# main.net
KiCad netlist of a schematic drawn in EAGLE
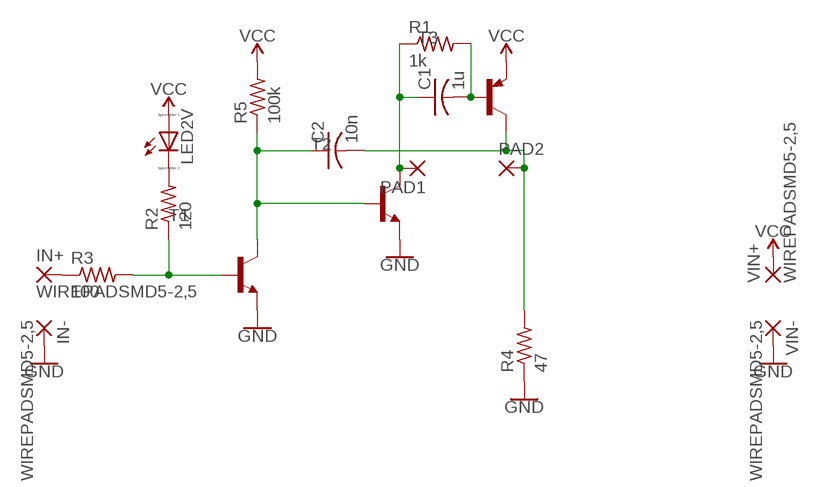
[diagram p0: schematic, sheet 1]

(export (version "E")
  (design (tool "Eeschema 10.0.6"))
  (components
    (comp (ref "C1")
      (value "1u")
      (footprint "eagle-import:C0603")
      (libsource (lib "eagle-import") (part "C-USC0603"))
    )
    (comp (ref "C2")
      (value "10n")
      (footprint "eagle-import:C0603")
      (libsource (lib "eagle-import") (part "C-USC0603"))
    )
    (comp (ref "IN+")
      (value "WIREPADSMD5-2,5")
      (footprint "eagle-import:5-2,5")
      (libsource (lib "eagle-import") (part "WIREPADSMD5-2,5"))
    )
    (comp (ref "IN-")
      (value "WIREPADSMD5-2,5")
      (footprint "eagle-import:5-2,5")
      (libsource (lib "eagle-import") (part "WIREPADSMD5-2,5"))
    )
    (comp (ref "LED2V")
      (value "LED_ESML0603")
      (footprint "eagle-import:LED_SML0603")
      (libsource (lib "eagle-import") (part "LED_ESML0603"))
    )
    (comp (ref "PAD1")
      (value "2,54/1,0")
      (footprint "eagle-import:2,54_1,0")
      (libsource (lib "eagle-import") (part "2,54/1,0"))
    )
    (comp (ref "PAD2")
      (value "2,54/1,0")
      (footprint "eagle-import:2,54_1,0")
      (libsource (lib "eagle-import") (part "2,54/1,0"))
    )
    (comp (ref "R1")
      (value "1k")
      (footprint "eagle-import:R0603")
      (libsource (lib "eagle-import") (part "R-US_R0603"))
    )
    (comp (ref "R2")
      (value "120")
      (footprint "eagle-import:R0603")
      (libsource (lib "eagle-import") (part "R-US_R0603"))
    )
    (comp (ref "R3")
      (value "100")
      (footprint "eagle-import:R0603")
      (libsource (lib "eagle-import") (part "R-US_R0603"))
    )
    (comp (ref "R4")
      (value "47")
      (footprint "eagle-import:R0603")
      (libsource (lib "eagle-import") (part "R-US_R0603"))
    )
    (comp (ref "R5")
      (value "100k")
      (footprint "eagle-import:R0603")
      (libsource (lib "eagle-import") (part "R-US_R0603"))
    )
    (comp (ref "T1")
      (value "MMBT3904LT1-NPN-SOT23-BEC")
      (footprint "eagle-import:SOT23-BEC")
      (libsource (lib "eagle-import") (part "-NPN-SOT23-BECMMBT3904LT1"))
    )
    (comp (ref "T2")
      (value "MMBT3904LT1-NPN-SOT23-BEC")
      (footprint "eagle-import:SOT23-BEC")
      (libsource (lib "eagle-import") (part "-NPN-SOT23-BECMMBT3904LT1"))
    )
    (comp (ref "T3")
      (value "MMBT3906LT1-PNP-SOT23-BEC")
      (footprint "eagle-import:SOT23-BEC")
      (libsource (lib "eagle-import") (part "-PNP-SOT23-BECMMBT3906LT1"))
    )
    (comp (ref "VIN+")
      (value "WIREPADSMD5-2,5")
      (footprint "eagle-import:5-2,5")
      (libsource (lib "eagle-import") (part "WIREPADSMD5-2,5"))
    )
    (comp (ref "VIN-")
      (value "WIREPADSMD5-2,5")
      (footprint "eagle-import:5-2,5")
      (libsource (lib "eagle-import") (part "WIREPADSMD5-2,5"))
    )
  )
  (nets
    (net (code "1") (name "GND") (class "Default")
      (node (ref "IN-") (pin "1") (pinfunction "P_1") (pintype "passive"))
      (node (ref "R4") (pin "1") (pinfunction "1_1") (pintype "passive"))
      (node (ref "T1") (pin "E") (pinfunction "E_E") (pintype "passive"))
      (node (ref "T2") (pin "E") (pinfunction "E_E") (pintype "passive"))
      (node (ref "VIN-") (pin "1") (pinfunction "P_1") (pintype "passive"))
    )
    (net (code "2") (name "Net-(C1-Pad2)") (class "Default")
      (node (ref "C1") (pin "2") (pinfunction "2_2") (pintype "passive"))
      (node (ref "R1") (pin "2") (pinfunction "2_2") (pintype "passive"))
      (node (ref "T3") (pin "B") (pinfunction "B_B") (pintype "passive"))
    )
    (net (code "3") (name "Net-(C2-Pad1)") (class "Default")
      (node (ref "C2") (pin "1") (pinfunction "1_1") (pintype "passive"))
      (node (ref "R5") (pin "1") (pinfunction "1_1") (pintype "passive"))
      (node (ref "T1") (pin "C") (pinfunction "C_C") (pintype "passive"))
      (node (ref "T2") (pin "B") (pinfunction "B_B") (pintype "passive"))
    )
    (net (code "4") (name "Net-(IN+-P)") (class "Default")
      (node (ref "IN+") (pin "1") (pinfunction "P_1") (pintype "passive"))
      (node (ref "R3") (pin "1") (pinfunction "1_1") (pintype "passive"))
    )
    (net (code "5") (name "Net-(LED2V-PadC)") (class "Default")
      (node (ref "LED2V") (pin "C") (pinfunction "C_C") (pintype "passive"))
      (node (ref "R2") (pin "2") (pinfunction "2_2") (pintype "passive"))
    )
    (net (code "6") (name "Net-(PAD1-P)") (class "Default")
      (node (ref "C1") (pin "1") (pinfunction "1_1") (pintype "passive"))
      (node (ref "PAD1") (pin "1") (pinfunction "P_1") (pintype "passive"))
      (node (ref "R1") (pin "1") (pinfunction "1_1") (pintype "passive"))
      (node (ref "T2") (pin "C") (pinfunction "C_C") (pintype "passive"))
    )
    (net (code "7") (name "Net-(PAD2-P)") (class "Default")
      (node (ref "C2") (pin "2") (pinfunction "2_2") (pintype "passive"))
      (node (ref "PAD2") (pin "1") (pinfunction "P_1") (pintype "passive"))
      (node (ref "R4") (pin "2") (pinfunction "2_2") (pintype "passive"))
      (node (ref "T3") (pin "C") (pinfunction "C_C") (pintype "passive"))
    )
    (net (code "8") (name "Net-(R2-Pad1)") (class "Default")
      (node (ref "R2") (pin "1") (pinfunction "1_1") (pintype "passive"))
      (node (ref "R3") (pin "2") (pinfunction "2_2") (pintype "passive"))
      (node (ref "T1") (pin "B") (pinfunction "B_B") (pintype "passive"))
    )
    (net (code "9") (name "VCC") (class "Default")
      (node (ref "LED2V") (pin "A") (pinfunction "A_A") (pintype "passive"))
      (node (ref "R5") (pin "2") (pinfunction "2_2") (pintype "passive"))
      (node (ref "T3") (pin "E") (pinfunction "E_E") (pintype "passive"))
      (node (ref "VIN+") (pin "1") (pinfunction "P_1") (pintype "passive"))
    )
  )
)
